# Chov3_led.net
KiCad netlist of a schematic drawn in Altium Designer
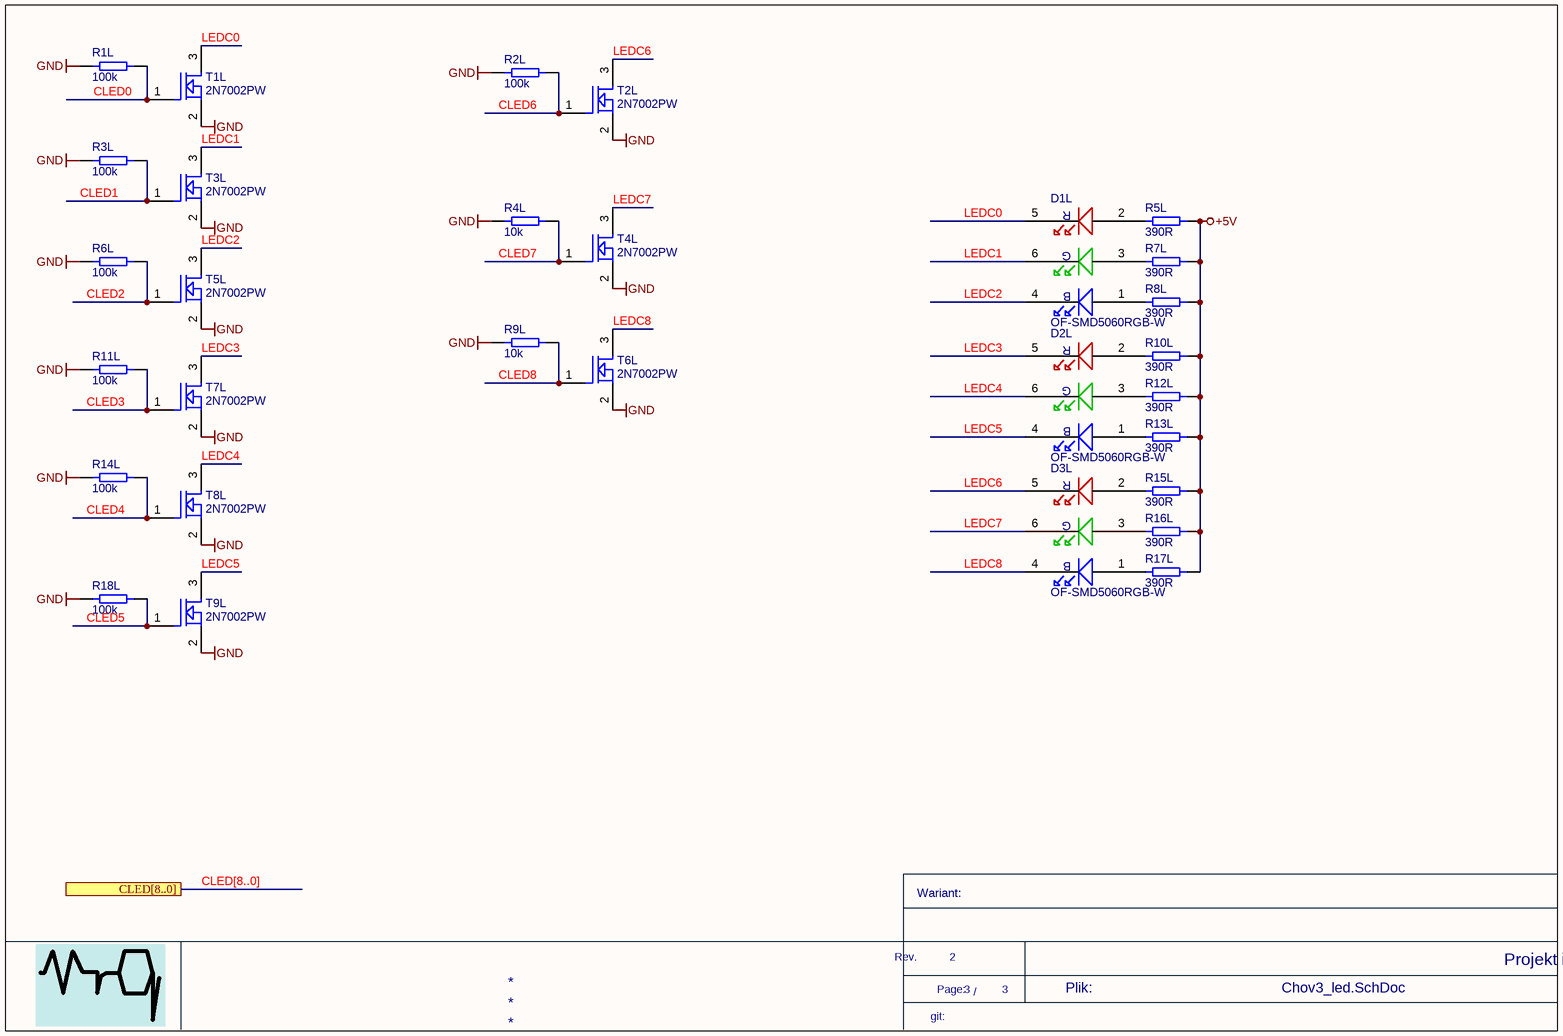
[diagram p0: Chov3_led.SchDoc]

(export (version "E")
  (design (tool "Eeschema 10.0.6"))
  (components
    (comp (ref "D1L")
      (value "OF-SMD5060RGB-W")
      (footprint "OF-SMD5060RGB-W")
      (libsource (lib "Parts") (part "OF-SMD5060RGB-W"))
    )
    (comp (ref "D2L")
      (value "OF-SMD5060RGB-W")
      (footprint "OF-SMD5060RGB-W")
      (libsource (lib "Parts") (part "OF-SMD5060RGB-W"))
    )
    (comp (ref "D3L")
      (value "OF-SMD5060RGB-W")
      (footprint "OF-SMD5060RGB-W")
      (libsource (lib "Parts") (part "OF-SMD5060RGB-W"))
    )
    (comp (ref "R1L")
      (value "0603SAF1003T5E")
      (footprint "0603-IPC")
      (fields (field (name "OTHERPARAMS") "100k") (field (name "TOLERANCE") "1%"))
      (libsource (lib "Parts") (part "R"))
    )
    (comp (ref "R2L")
      (value "0603SAF1003T5E")
      (footprint "0603-IPC")
      (fields (field (name "OTHERPARAMS") "100k") (field (name "TOLERANCE") "1%"))
      (libsource (lib "Parts") (part "R"))
    )
    (comp (ref "R3L")
      (value "0603SAF1003T5E")
      (footprint "0603-IPC")
      (fields (field (name "OTHERPARAMS") "100k") (field (name "TOLERANCE") "1%"))
      (libsource (lib "Parts") (part "R"))
    )
    (comp (ref "R4L")
      (value "0603WGF10KT5E")
      (footprint "0603-IPC")
      (fields (field (name "OTHERPARAMS") "10k") (field (name "TOLERANCE") "1%"))
      (libsource (lib "Parts") (part "R"))
    )
    (comp (ref "R5L")
      (value "0805WAF 390R T5E")
      (footprint "0805")
      (fields (field (name "OTHERPARAMS") "390R") (field (name "TOLERANCE") "1%"))
      (libsource (lib "Parts") (part "R"))
    )
    (comp (ref "R6L")
      (value "0603SAF1003T5E")
      (footprint "0603-IPC")
      (fields (field (name "OTHERPARAMS") "100k") (field (name "TOLERANCE") "1%"))
      (libsource (lib "Parts") (part "R"))
    )
    (comp (ref "R7L")
      (value "0805WAF 390R T5E")
      (footprint "0805")
      (fields (field (name "OTHERPARAMS") "390R") (field (name "TOLERANCE") "1%"))
      (libsource (lib "Parts") (part "R"))
    )
    (comp (ref "R8L")
      (value "0805WAF 390R T5E")
      (footprint "0805")
      (fields (field (name "OTHERPARAMS") "390R") (field (name "TOLERANCE") "1%"))
      (libsource (lib "Parts") (part "R"))
    )
    (comp (ref "R9L")
      (value "0603WGF10KT5E")
      (footprint "0603-IPC")
      (fields (field (name "OTHERPARAMS") "10k") (field (name "TOLERANCE") "1%"))
      (libsource (lib "Parts") (part "R"))
    )
    (comp (ref "R10L")
      (value "0805WAF 390R T5E")
      (footprint "0805")
      (fields (field (name "OTHERPARAMS") "390R") (field (name "TOLERANCE") "1%"))
      (libsource (lib "Parts") (part "R"))
    )
    (comp (ref "R11L")
      (value "0603SAF1003T5E")
      (footprint "0603-IPC")
      (fields (field (name "OTHERPARAMS") "100k") (field (name "TOLERANCE") "1%"))
      (libsource (lib "Parts") (part "R"))
    )
    (comp (ref "R12L")
      (value "0805WAF 390R T5E")
      (footprint "0805")
      (fields (field (name "OTHERPARAMS") "390R") (field (name "TOLERANCE") "1%"))
      (libsource (lib "Parts") (part "R"))
    )
    (comp (ref "R13L")
      (value "0805WAF 390R T5E")
      (footprint "0805")
      (fields (field (name "OTHERPARAMS") "390R") (field (name "TOLERANCE") "1%"))
      (libsource (lib "Parts") (part "R"))
    )
    (comp (ref "R14L")
      (value "0603SAF1003T5E")
      (footprint "0603-IPC")
      (fields (field (name "OTHERPARAMS") "100k") (field (name "TOLERANCE") "1%"))
      (libsource (lib "Parts") (part "R"))
    )
    (comp (ref "R15L")
      (value "0805WAF 390R T5E")
      (footprint "0805")
      (fields (field (name "OTHERPARAMS") "390R") (field (name "TOLERANCE") "1%"))
      (libsource (lib "Parts") (part "R"))
    )
    (comp (ref "R16L")
      (value "0805WAF 390R T5E")
      (footprint "0805")
      (fields (field (name "OTHERPARAMS") "390R") (field (name "TOLERANCE") "1%"))
      (libsource (lib "Parts") (part "R"))
    )
    (comp (ref "R17L")
      (value "0805WAF 390R T5E")
      (footprint "0805")
      (fields (field (name "OTHERPARAMS") "390R") (field (name "TOLERANCE") "1%"))
      (libsource (lib "Parts") (part "R"))
    )
    (comp (ref "R18L")
      (value "0603SAF1003T5E")
      (footprint "0603-IPC")
      (fields (field (name "OTHERPARAMS") "100k") (field (name "TOLERANCE") "1%"))
      (libsource (lib "Parts") (part "R"))
    )
    (comp (ref "T1L")
      (value "2N7002PW")
      (footprint "SOT323-3_FLOW")
      (libsource (lib "Parts") (part "MOSFET_N_SOT23-3"))
    )
    (comp (ref "T2L")
      (value "2N7002PW")
      (footprint "SOT323-3_FLOW")
      (libsource (lib "Parts") (part "MOSFET_N_SOT23-3"))
    )
    (comp (ref "T3L")
      (value "2N7002PW")
      (footprint "SOT323-3_FLOW")
      (libsource (lib "Parts") (part "MOSFET_N_SOT23-3"))
    )
    (comp (ref "T4L")
      (value "2N7002PW")
      (footprint "SOT323-3_FLOW")
      (libsource (lib "Parts") (part "MOSFET_N_SOT23-3"))
    )
    (comp (ref "T5L")
      (value "2N7002PW")
      (footprint "SOT323-3_FLOW")
      (libsource (lib "Parts") (part "MOSFET_N_SOT23-3"))
    )
    (comp (ref "T6L")
      (value "2N7002PW")
      (footprint "SOT323-3_FLOW")
      (libsource (lib "Parts") (part "MOSFET_N_SOT23-3"))
    )
    (comp (ref "T7L")
      (value "2N7002PW")
      (footprint "SOT323-3_FLOW")
      (libsource (lib "Parts") (part "MOSFET_N_SOT23-3"))
    )
    (comp (ref "T8L")
      (value "2N7002PW")
      (footprint "SOT323-3_FLOW")
      (libsource (lib "Parts") (part "MOSFET_N_SOT23-3"))
    )
    (comp (ref "T9L")
      (value "2N7002PW")
      (footprint "SOT323-3_FLOW")
      (libsource (lib "Parts") (part "MOSFET_N_SOT23-3"))
    )
  )
  (nets
    (net (code "1") (name "+5V") (class "Default")
      (node (ref "R10L") (pin "2") (pinfunction "2_2") (pintype "passive"))
      (node (ref "R12L") (pin "2") (pinfunction "2_2") (pintype "passive"))
      (node (ref "R13L") (pin "2") (pinfunction "2_2") (pintype "passive"))
      (node (ref "R15L") (pin "2") (pinfunction "2_2") (pintype "passive"))
      (node (ref "R16L") (pin "2") (pinfunction "2_2") (pintype "passive"))
      (node (ref "R17L") (pin "2") (pinfunction "2_2") (pintype "passive"))
      (node (ref "R5L") (pin "2") (pinfunction "2_2") (pintype "passive"))
      (node (ref "R7L") (pin "2") (pinfunction "2_2") (pintype "passive"))
      (node (ref "R8L") (pin "2") (pinfunction "2_2") (pintype "passive"))
    )
    (net (code "2") (name "/CLED0") (class "Default")
      (node (ref "R1L") (pin "2") (pinfunction "2_2") (pintype "passive"))
      (node (ref "T1L") (pin "1") (pinfunction "GATE_1") (pintype "passive"))
    )
    (net (code "3") (name "/CLED1") (class "Default")
      (node (ref "R3L") (pin "2") (pinfunction "2_2") (pintype "passive"))
      (node (ref "T3L") (pin "1") (pinfunction "GATE_1") (pintype "passive"))
    )
    (net (code "4") (name "/CLED2") (class "Default")
      (node (ref "R6L") (pin "2") (pinfunction "2_2") (pintype "passive"))
      (node (ref "T5L") (pin "1") (pinfunction "GATE_1") (pintype "passive"))
    )
    (net (code "5") (name "/CLED3") (class "Default")
      (node (ref "R11L") (pin "2") (pinfunction "2_2") (pintype "passive"))
      (node (ref "T7L") (pin "1") (pinfunction "GATE_1") (pintype "passive"))
    )
    (net (code "6") (name "/CLED4") (class "Default")
      (node (ref "R14L") (pin "2") (pinfunction "2_2") (pintype "passive"))
      (node (ref "T8L") (pin "1") (pinfunction "GATE_1") (pintype "passive"))
    )
    (net (code "7") (name "/CLED5") (class "Default")
      (node (ref "R18L") (pin "2") (pinfunction "2_2") (pintype "passive"))
      (node (ref "T9L") (pin "1") (pinfunction "GATE_1") (pintype "passive"))
    )
    (net (code "8") (name "/CLED6") (class "Default")
      (node (ref "R2L") (pin "2") (pinfunction "2_2") (pintype "passive"))
      (node (ref "T2L") (pin "1") (pinfunction "GATE_1") (pintype "passive"))
    )
    (net (code "9") (name "/CLED7") (class "Default")
      (node (ref "R4L") (pin "2") (pinfunction "2_2") (pintype "passive"))
      (node (ref "T4L") (pin "1") (pinfunction "GATE_1") (pintype "passive"))
    )
    (net (code "10") (name "/CLED8") (class "Default")
      (node (ref "R9L") (pin "2") (pinfunction "2_2") (pintype "passive"))
      (node (ref "T6L") (pin "1") (pinfunction "GATE_1") (pintype "passive"))
    )
    (net (code "12") (name "/LEDC0") (class "Default")
      (node (ref "D1L") (pin "5") (pinfunction "CATH_5") (pintype "passive"))
      (node (ref "T1L") (pin "3") (pinfunction "DRAIN_3") (pintype "passive"))
    )
    (net (code "13") (name "/LEDC1") (class "Default")
      (node (ref "D1L") (pin "6") (pinfunction "CATH_6") (pintype "passive"))
      (node (ref "T3L") (pin "3") (pinfunction "DRAIN_3") (pintype "passive"))
    )
    (net (code "14") (name "/LEDC2") (class "Default")
      (node (ref "D1L") (pin "4") (pinfunction "CATH_4") (pintype "passive"))
      (node (ref "T5L") (pin "3") (pinfunction "DRAIN_3") (pintype "passive"))
    )
    (net (code "15") (name "/LEDC3") (class "Default")
      (node (ref "D2L") (pin "5") (pinfunction "CATH_5") (pintype "passive"))
      (node (ref "T7L") (pin "3") (pinfunction "DRAIN_3") (pintype "passive"))
    )
    (net (code "16") (name "/LEDC4") (class "Default")
      (node (ref "D2L") (pin "6") (pinfunction "CATH_6") (pintype "passive"))
      (node (ref "T8L") (pin "3") (pinfunction "DRAIN_3") (pintype "passive"))
    )
    (net (code "17") (name "/LEDC5") (class "Default")
      (node (ref "D2L") (pin "4") (pinfunction "CATH_4") (pintype "passive"))
      (node (ref "T9L") (pin "3") (pinfunction "DRAIN_3") (pintype "passive"))
    )
    (net (code "18") (name "/LEDC6") (class "Default")
      (node (ref "D3L") (pin "5") (pinfunction "CATH_5") (pintype "passive"))
      (node (ref "T2L") (pin "3") (pinfunction "DRAIN_3") (pintype "passive"))
    )
    (net (code "19") (name "/LEDC7") (class "Default")
      (node (ref "D3L") (pin "6") (pinfunction "CATH_6") (pintype "passive"))
      (node (ref "T4L") (pin "3") (pinfunction "DRAIN_3") (pintype "passive"))
    )
    (net (code "20") (name "/LEDC8") (class "Default")
      (node (ref "D3L") (pin "4") (pinfunction "CATH_4") (pintype "passive"))
      (node (ref "T6L") (pin "3") (pinfunction "DRAIN_3") (pintype "passive"))
    )
    (net (code "21") (name "GND") (class "Default")
      (node (ref "R11L") (pin "1") (pinfunction "1_1") (pintype "passive"))
      (node (ref "R14L") (pin "1") (pinfunction "1_1") (pintype "passive"))
      (node (ref "R18L") (pin "1") (pinfunction "1_1") (pintype "passive"))
      (node (ref "R1L") (pin "1") (pinfunction "1_1") (pintype "passive"))
      (node (ref "R2L") (pin "1") (pinfunction "1_1") (pintype "passive"))
      (node (ref "R3L") (pin "1") (pinfunction "1_1") (pintype "passive"))
      (node (ref "R4L") (pin "1") (pinfunction "1_1") (pintype "passive"))
      (node (ref "R6L") (pin "1") (pinfunction "1_1") (pintype "passive"))
      (node (ref "R9L") (pin "1") (pinfunction "1_1") (pintype "passive"))
      (node (ref "T1L") (pin "2") (pinfunction "SOURCE_2") (pintype "passive"))
      (node (ref "T2L") (pin "2") (pinfunction "SOURCE_2") (pintype "passive"))
      (node (ref "T3L") (pin "2") (pinfunction "SOURCE_2") (pintype "passive"))
      (node (ref "T4L") (pin "2") (pinfunction "SOURCE_2") (pintype "passive"))
      (node (ref "T5L") (pin "2") (pinfunction "SOURCE_2") (pintype "passive"))
      (node (ref "T6L") (pin "2") (pinfunction "SOURCE_2") (pintype "passive"))
      (node (ref "T7L") (pin "2") (pinfunction "SOURCE_2") (pintype "passive"))
      (node (ref "T8L") (pin "2") (pinfunction "SOURCE_2") (pintype "passive"))
      (node (ref "T9L") (pin "2") (pinfunction "SOURCE_2") (pintype "passive"))
    )
    (net (code "22") (name "Net-(D1L-ANOD-Pad1)") (class "Default")
      (node (ref "D1L") (pin "1") (pinfunction "ANOD_1") (pintype "passive"))
      (node (ref "R8L") (pin "1") (pinfunction "1_1") (pintype "passive"))
    )
    (net (code "23") (name "Net-(D1L-ANOD-Pad2)") (class "Default")
      (node (ref "D1L") (pin "2") (pinfunction "ANOD_2") (pintype "passive"))
      (node (ref "R5L") (pin "1") (pinfunction "1_1") (pintype "passive"))
    )
    (net (code "24") (name "Net-(D1L-ANOD-Pad3)") (class "Default")
      (node (ref "D1L") (pin "3") (pinfunction "ANOD_3") (pintype "passive"))
      (node (ref "R7L") (pin "1") (pinfunction "1_1") (pintype "passive"))
    )
    (net (code "25") (name "Net-(D2L-ANOD-Pad1)") (class "Default")
      (node (ref "D2L") (pin "1") (pinfunction "ANOD_1") (pintype "passive"))
      (node (ref "R13L") (pin "1") (pinfunction "1_1") (pintype "passive"))
    )
    (net (code "26") (name "Net-(D2L-ANOD-Pad2)") (class "Default")
      (node (ref "D2L") (pin "2") (pinfunction "ANOD_2") (pintype "passive"))
      (node (ref "R10L") (pin "1") (pinfunction "1_1") (pintype "passive"))
    )
    (net (code "27") (name "Net-(D2L-ANOD-Pad3)") (class "Default")
      (node (ref "D2L") (pin "3") (pinfunction "ANOD_3") (pintype "passive"))
      (node (ref "R12L") (pin "1") (pinfunction "1_1") (pintype "passive"))
    )
    (net (code "28") (name "Net-(D3L-ANOD-Pad1)") (class "Default")
      (node (ref "D3L") (pin "1") (pinfunction "ANOD_1") (pintype "passive"))
      (node (ref "R17L") (pin "1") (pinfunction "1_1") (pintype "passive"))
    )
    (net (code "29") (name "Net-(D3L-ANOD-Pad2)") (class "Default")
      (node (ref "D3L") (pin "2") (pinfunction "ANOD_2") (pintype "passive"))
      (node (ref "R15L") (pin "1") (pinfunction "1_1") (pintype "passive"))
    )
    (net (code "30") (name "Net-(D3L-ANOD-Pad3)") (class "Default")
      (node (ref "D3L") (pin "3") (pinfunction "ANOD_3") (pintype "passive"))
      (node (ref "R16L") (pin "1") (pinfunction "1_1") (pintype "passive"))
    )
  )
)
